# 202011AWSNP02.net
KiCad netlist of a schematic drawn in Altium Designer
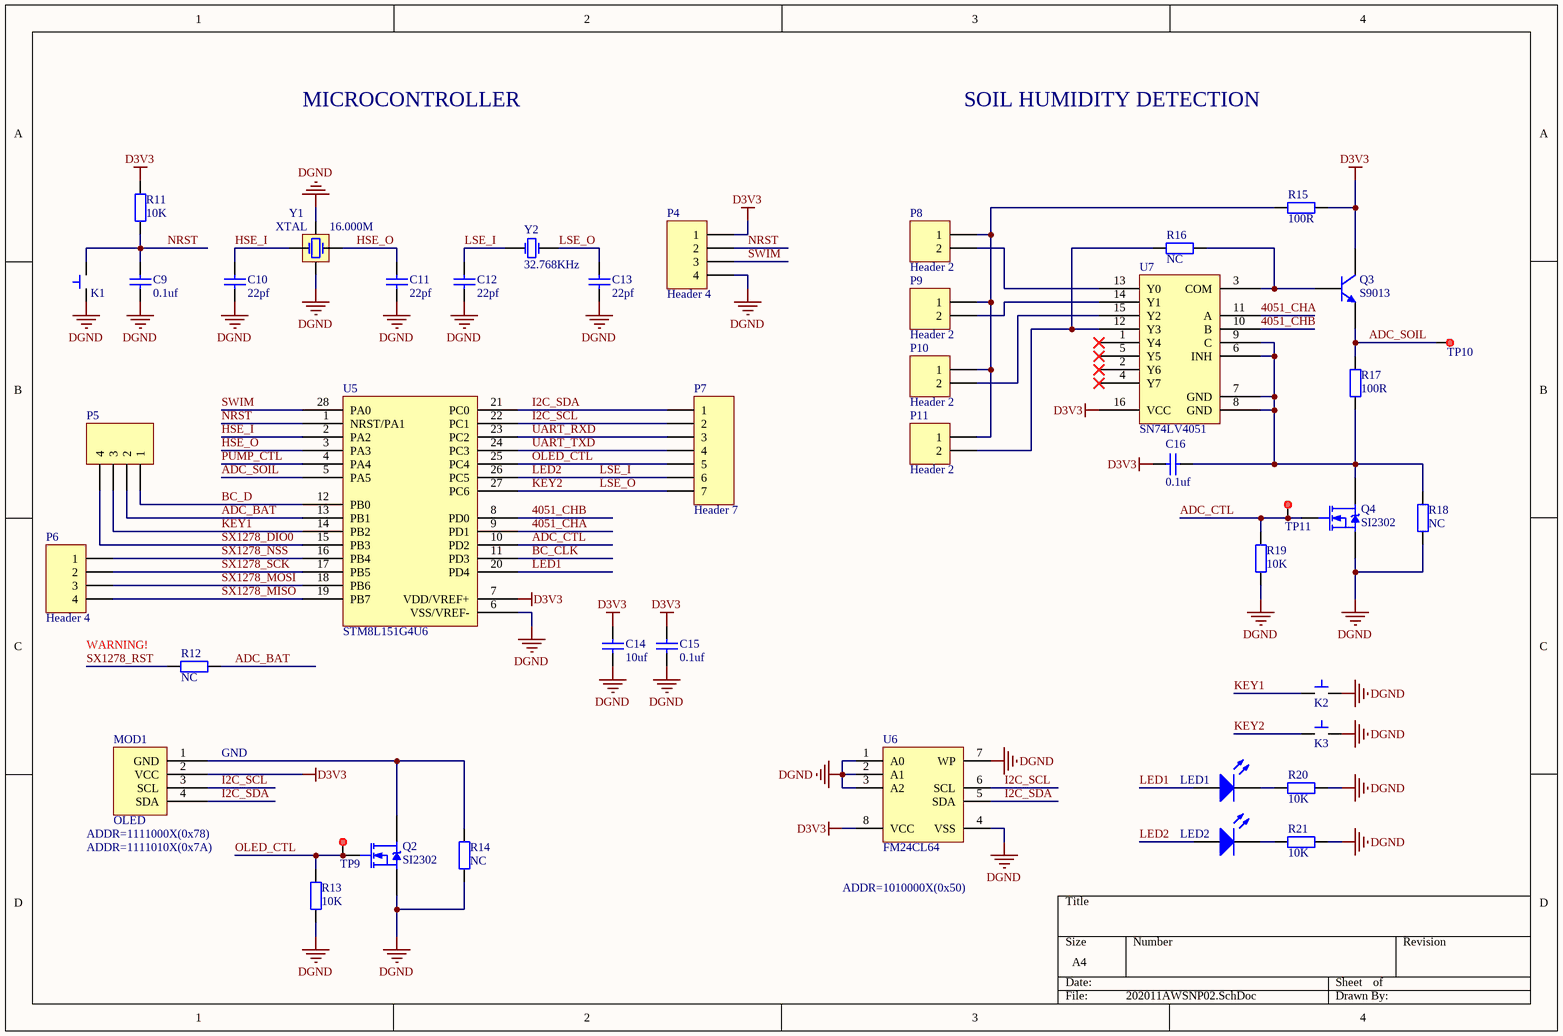
[diagram p0: 202011AWSNP02.SchDoc]

(export (version "E")
  (design (tool "Eeschema 10.0.6"))
  (components
    (comp (ref "C9")
      (value "0.1uf")
      (footprint "C0805")
      (fields (field (name "Comment") "Cap"))
      (libsource (lib "carrot_lib") (part "Cap"))
    )
    (comp (ref "C10")
      (value "22pf")
      (footprint "C0805")
      (fields (field (name "Comment") "Cap"))
      (libsource (lib "carrot_lib") (part "Cap"))
    )
    (comp (ref "C11")
      (value "22pf")
      (footprint "C0805")
      (fields (field (name "Comment") "Cap"))
      (libsource (lib "carrot_lib") (part "Cap"))
    )
    (comp (ref "C12")
      (value "22pf")
      (footprint "C0805")
      (fields (field (name "Comment") "Cap"))
      (libsource (lib "carrot_lib") (part "Cap"))
    )
    (comp (ref "C13")
      (value "22pf")
      (footprint "C0805")
      (fields (field (name "Comment") "Cap"))
      (libsource (lib "carrot_lib") (part "Cap"))
    )
    (comp (ref "C14")
      (value "10uf")
      (footprint "C0805")
      (fields (field (name "Comment") "Cap"))
      (libsource (lib "carrot_lib") (part "Cap"))
    )
    (comp (ref "C15")
      (value "0.1uf")
      (footprint "C0805")
      (fields (field (name "Comment") "Cap"))
      (libsource (lib "carrot_lib") (part "Cap"))
    )
    (comp (ref "C16")
      (value "0.1uf")
      (footprint "C0805")
      (fields (field (name "Comment") "Cap"))
      (libsource (lib "carrot_lib") (part "Cap"))
    )
    (comp (ref "K1")
      (value "Button")
      (footprint "Button-SMT-Small")
      (description "轻触开关")
      (libsource (lib "carrot_lib") (part "Button"))
    )
    (comp (ref "K2")
      (value "Button")
      (footprint "Button-SMT-Small")
      (description "轻触开关")
      (libsource (lib "carrot_lib") (part "Button"))
    )
    (comp (ref "K3")
      (value "Button")
      (footprint "Button-SMT-Small")
      (description "轻触开关")
      (libsource (lib "carrot_lib") (part "Button"))
    )
    (comp (ref "LED1") (value "LED") (footprint "LED1206") (libsource (lib "carrot_lib") (part "LED")))
    (comp (ref "LED2") (value "LED") (footprint "LED1206") (libsource (lib "carrot_lib") (part "LED")))
    (comp (ref "MOD1")
      (value "OLED")
      (footprint "MODULE OLED-4P-0.96")
      (description "OLED显示模块")
      (libsource (lib "carrot_lib") (part "Module OLED"))
    )
    (comp (ref "P4")
      (value "Header 4")
      (footprint "HDR1X4")
      (description "Header, 4-Pin")
      (fields (field (name "PUBLISHER") "Altium Limited"))
      (libsource (lib "Miscellaneous Connectors") (part "Header 4"))
    )
    (comp (ref "P5")
      (value "Header 4")
      (footprint "HDR1X4")
      (description "Header, 4-Pin")
      (fields (field (name "PUBLISHER") "Altium Limited"))
      (libsource (lib "") (part "Header 4_1"))
    )
    (comp (ref "P6")
      (value "Header 4")
      (footprint "HDR1X4")
      (description "Header, 4-Pin")
      (fields (field (name "PUBLISHER") "Altium Limited"))
      (libsource (lib "Miscellaneous Connectors") (part "Header 4"))
    )
    (comp (ref "P7")
      (value "Header 7")
      (footprint "HDR1X7")
      (description "Header, 7-Pin")
      (fields (field (name "PUBLISHER") "Altium Limited"))
      (libsource (lib "Miscellaneous Connectors") (part "Header 7"))
    )
    (comp (ref "P8")
      (value "Header 2")
      (footprint "HDR1X2")
      (description "Header, 2-Pin")
      (fields (field (name "PUBLISHER") "Altium Limited"))
      (libsource (lib "Miscellaneous Connectors") (part "Header 2"))
    )
    (comp (ref "P9")
      (value "Header 2")
      (footprint "HDR1X2")
      (description "Header, 2-Pin")
      (fields (field (name "PUBLISHER") "Altium Limited"))
      (libsource (lib "Miscellaneous Connectors") (part "Header 2"))
    )
    (comp (ref "P10")
      (value "Header 2")
      (footprint "HDR1X2")
      (description "Header, 2-Pin")
      (fields (field (name "PUBLISHER") "Altium Limited"))
      (libsource (lib "Miscellaneous Connectors") (part "Header 2"))
    )
    (comp (ref "P11")
      (value "Header 2")
      (footprint "HDR1X2")
      (description "Header, 2-Pin")
      (fields (field (name "PUBLISHER") "Altium Limited"))
      (libsource (lib "Miscellaneous Connectors") (part "Header 2"))
    )
    (comp (ref "Q2")
      (value "SI2302")
      (footprint "SI2302-SOT23")
      (description "N-Channel 20 V (D-S) MOSFET")
      (libsource (lib "carrot_lib") (part "SI2302"))
    )
    (comp (ref "Q3")
      (value "S9013")
      (footprint "SOT-23")
      (description "NPN General Purpose Amplifier")
      (libsource (lib "carrot_lib") (part "NPN"))
    )
    (comp (ref "Q4")
      (value "SI2302")
      (footprint "SI2302-SOT23")
      (description "N-Channel 20 V (D-S) MOSFET")
      (libsource (lib "carrot_lib") (part "SI2302"))
    )
    (comp (ref "R11")
      (value "10K")
      (footprint "R0805")
      (description "电阻")
      (fields (field (name "Comment") "Res"))
      (libsource (lib "carrot_lib") (part "Res"))
    )
    (comp (ref "R12")
      (value "NC")
      (footprint "R0805")
      (description "电阻")
      (fields (field (name "Comment") "Res"))
      (libsource (lib "carrot_lib") (part "Res"))
    )
    (comp (ref "R13")
      (value "10K")
      (footprint "R0805")
      (description "电阻")
      (fields (field (name "Comment") "Res"))
      (libsource (lib "") (part "Res_1"))
    )
    (comp (ref "R14")
      (value "NC")
      (footprint "R0805")
      (description "电阻")
      (fields (field (name "Comment") "Res"))
      (libsource (lib "") (part "Res_1"))
    )
    (comp (ref "R15")
      (value "100R")
      (footprint "R0805")
      (description "电阻")
      (fields (field (name "Comment") "Res"))
      (libsource (lib "") (part "Res_2"))
    )
    (comp (ref "R16")
      (value "NC")
      (footprint "R0805")
      (description "电阻")
      (fields (field (name "Comment") "Res"))
      (libsource (lib "") (part "Res_2"))
    )
    (comp (ref "R17")
      (value "100R")
      (footprint "R0805")
      (description "电阻")
      (fields (field (name "Comment") "Res"))
      (libsource (lib "") (part "Res_1"))
    )
    (comp (ref "R18")
      (value "NC")
      (footprint "R0805")
      (description "电阻")
      (fields (field (name "Comment") "Res"))
      (libsource (lib "") (part "Res_1"))
    )
    (comp (ref "R19")
      (value "10K")
      (footprint "R0805")
      (description "电阻")
      (fields (field (name "Comment") "Res"))
      (libsource (lib "") (part "Res_1"))
    )
    (comp (ref "R20")
      (value "10K")
      (footprint "R0805")
      (description "电阻")
      (fields (field (name "Comment") "Res"))
      (libsource (lib "") (part "Res_3"))
    )
    (comp (ref "R21")
      (value "10K")
      (footprint "R0805")
      (description "电阻")
      (fields (field (name "Comment") "Res"))
      (libsource (lib "") (part "Res_3"))
    )
    (comp (ref "TP9")
      (value "TestPoint")
      (footprint "TestPoint-R30")
      (description "测试点")
      (libsource (lib "carrot_lib") (part "TestPoint"))
    )
    (comp (ref "TP10")
      (value "TestPoint")
      (footprint "TestPoint-R30")
      (description "测试点")
      (libsource (lib "carrot_lib") (part "TestPoint"))
    )
    (comp (ref "TP11")
      (value "TestPoint")
      (footprint "TestPoint-R30")
      (description "测试点")
      (libsource (lib "carrot_lib") (part "TestPoint"))
    )
    (comp (ref "U5")
      (value "STM8L151G4U6")
      (footprint "STM8L151G4U6-UFQFN28")
      (libsource (lib "carrot_lib") (part "STM8L151G4U6"))
    )
    (comp (ref "U6")
      (value "FM24CL64")
      (footprint "FM24CL64-SOIC8")
      (description "64Kb Serial 3V FRAM Memory")
      (libsource (lib "carrot_lib") (part "FM24CL64"))
    )
    (comp (ref "U7")
      (value "SN74LV4051")
      (footprint "SN74LV4051-TSSOP16")
      (description "SN74LV4051A 8-Channel Analog Multiplexers and Demultiplexers")
      (libsource (lib "carrot_lib") (part "SN74LV4051"))
    )
    (comp (ref "Y1")
      (value "XTAL")
      (footprint "XTAL-3225")
      (description "无源晶振")
      (fields (field (name "ALTIUM_VALUE") "16.000M"))
      (libsource (lib "carrot_lib") (part "XTAL3"))
    )
    (comp (ref "Y2")
      (value "32.768KHz")
      (footprint "XTAL-3215")
      (description "Crystal Oscillator")
      (fields (field (name "Comment") "XTAL"))
      (libsource (lib "carrot_lib") (part "XTAL"))
    )
  )
  (nets
    (net (code "1") (name "/4051_CHA") (class "Default")
      (node (ref "U5") (pin "9") (pinfunction "PD1_9") (pintype "passive"))
      (node (ref "U7") (pin "11") (pinfunction "A_11") (pintype "passive"))
    )
    (net (code "2") (name "/4051_CHB") (class "Default")
      (node (ref "U5") (pin "8") (pinfunction "PD0_8") (pintype "passive"))
      (node (ref "U7") (pin "10") (pinfunction "B_10") (pintype "passive"))
    )
    (net (code "3") (name "/ADC_BAT") (class "Default")
      (node (ref "P5") (pin "2") (pinfunction "2_2") (pintype "passive"))
      (node (ref "R12") (pin "1") (pinfunction "1_1") (pintype "passive"))
      (node (ref "U5") (pin "13") (pinfunction "PB1_13") (pintype "passive"))
    )
    (net (code "4") (name "/ADC_CTL") (class "Default")
      (node (ref "Q4") (pin "1") (pinfunction "G_1") (pintype "passive"))
      (node (ref "R19") (pin "2") (pinfunction "2_2") (pintype "passive"))
      (node (ref "TP11") (pin "1") (pinfunction "1_1") (pintype "passive"))
      (node (ref "U5") (pin "10") (pinfunction "PD2_10") (pintype "passive"))
    )
    (net (code "5") (name "/ADC_SOIL") (class "Default")
      (node (ref "Q3") (pin "E") (pinfunction "E_E") (pintype "passive"))
      (node (ref "R17") (pin "2") (pinfunction "2_2") (pintype "passive"))
      (node (ref "TP10") (pin "1") (pinfunction "1_1") (pintype "passive"))
      (node (ref "U5") (pin "5") (pinfunction "PA5_5") (pintype "passive"))
    )
    (net (code "6") (name "/BC_CLK") (class "Default")
      (node (ref "U5") (pin "11") (pinfunction "PD3_11") (pintype "passive"))
    )
    (net (code "7") (name "/BC_D") (class "Default")
      (node (ref "P5") (pin "1") (pinfunction "1_1") (pintype "passive"))
      (node (ref "U5") (pin "12") (pinfunction "PB0_12") (pintype "passive"))
    )
    (net (code "8") (name "/HSE_I") (class "Default")
      (node (ref "C10") (pin "2") (pinfunction "2_2") (pintype "passive"))
      (node (ref "U5") (pin "2") (pinfunction "PA2_2") (pintype "passive"))
      (node (ref "Y1") (pin "1") (pinfunction "OSC1_1") (pintype "passive"))
    )
    (net (code "9") (name "/HSE_O") (class "Default")
      (node (ref "C11") (pin "2") (pinfunction "2_2") (pintype "passive"))
      (node (ref "U5") (pin "3") (pinfunction "PA3_3") (pintype "passive"))
      (node (ref "Y1") (pin "3") (pinfunction "OSC2_3") (pintype "passive"))
    )
    (net (code "10") (name "/I2C_SCL") (class "Default")
      (node (ref "MOD1") (pin "3") (pinfunction "SCL_3") (pintype "passive"))
      (node (ref "P7") (pin "2") (pinfunction "2_2") (pintype "passive"))
      (node (ref "U5") (pin "22") (pinfunction "PC1_22") (pintype "passive"))
      (node (ref "U6") (pin "6") (pinfunction "SCL_6") (pintype "passive"))
    )
    (net (code "11") (name "/I2C_SDA") (class "Default")
      (node (ref "MOD1") (pin "4") (pinfunction "SDA_4") (pintype "passive"))
      (node (ref "P7") (pin "1") (pinfunction "1_1") (pintype "passive"))
      (node (ref "U5") (pin "21") (pinfunction "PC0_21") (pintype "passive"))
      (node (ref "U6") (pin "5") (pinfunction "SDA_5") (pintype "passive"))
    )
    (net (code "12") (name "/KEY1") (class "Default")
      (node (ref "K2") (pin "1") (pinfunction "IN_1") (pintype "passive"))
      (node (ref "P5") (pin "3") (pinfunction "3_3") (pintype "passive"))
      (node (ref "U5") (pin "14") (pinfunction "PB2_14") (pintype "passive"))
    )
    (net (code "13") (name "/KEY2") (class "Default")
      (node (ref "C13") (pin "2") (pinfunction "2_2") (pintype "passive"))
      (node (ref "K3") (pin "1") (pinfunction "IN_1") (pintype "passive"))
      (node (ref "P7") (pin "7") (pinfunction "7_7") (pintype "passive"))
      (node (ref "U5") (pin "27") (pinfunction "PC6_27") (pintype "passive"))
      (node (ref "Y2") (pin "2") (pinfunction "OSC2_2") (pintype "passive"))
    )
    (net (code "14") (name "/LED1") (class "Default")
      (node (ref "LED1") (pin "1") (pinfunction "A_1") (pintype "passive"))
      (node (ref "U5") (pin "20") (pinfunction "PD4_20") (pintype "passive"))
    )
    (net (code "15") (name "/LED2") (class "Default")
      (node (ref "C12") (pin "2") (pinfunction "2_2") (pintype "passive"))
      (node (ref "LED2") (pin "1") (pinfunction "A_1") (pintype "passive"))
      (node (ref "P7") (pin "6") (pinfunction "6_6") (pintype "passive"))
      (node (ref "U5") (pin "26") (pinfunction "PC5_26") (pintype "passive"))
      (node (ref "Y2") (pin "1") (pinfunction "OSC1_1") (pintype "passive"))
    )
    (net (code "16") (name "/NRST") (class "Default")
      (node (ref "C9") (pin "2") (pinfunction "2_2") (pintype "passive"))
      (node (ref "K1") (pin "1") (pinfunction "IN_1") (pintype "passive"))
      (node (ref "P4") (pin "2") (pinfunction "2_2") (pintype "passive"))
      (node (ref "R11") (pin "2") (pinfunction "2_2") (pintype "passive"))
      (node (ref "U5") (pin "1") (pinfunction "NRST/PA1_1") (pintype "passive"))
    )
    (net (code "17") (name "/OLED_CTL") (class "Default")
      (node (ref "P7") (pin "5") (pinfunction "5_5") (pintype "passive"))
      (node (ref "Q2") (pin "1") (pinfunction "G_1") (pintype "passive"))
      (node (ref "R13") (pin "2") (pinfunction "2_2") (pintype "passive"))
      (node (ref "TP9") (pin "1") (pinfunction "1_1") (pintype "passive"))
      (node (ref "U5") (pin "25") (pinfunction "PC4_25") (pintype "passive"))
    )
    (net (code "18") (name "/PUMP_CTL") (class "Default")
      (node (ref "U5") (pin "4") (pinfunction "PA4_4") (pintype "passive"))
    )
    (net (code "19") (name "/SWIM") (class "Default")
      (node (ref "P4") (pin "3") (pinfunction "3_3") (pintype "passive"))
      (node (ref "U5") (pin "28") (pinfunction "PA0_28") (pintype "passive"))
    )
    (net (code "20") (name "/SX1278_DIO0") (class "Default")
      (node (ref "P5") (pin "4") (pinfunction "4_4") (pintype "passive"))
      (node (ref "U5") (pin "15") (pinfunction "PB3_15") (pintype "passive"))
    )
    (net (code "21") (name "/SX1278_MISO") (class "Default")
      (node (ref "P6") (pin "4") (pinfunction "4_4") (pintype "passive"))
      (node (ref "U5") (pin "19") (pinfunction "PB7_19") (pintype "passive"))
    )
    (net (code "22") (name "/SX1278_MOSI") (class "Default")
      (node (ref "P6") (pin "3") (pinfunction "3_3") (pintype "passive"))
      (node (ref "U5") (pin "18") (pinfunction "PB6_18") (pintype "passive"))
    )
    (net (code "23") (name "/SX1278_NSS") (class "Default")
      (node (ref "P6") (pin "1") (pinfunction "1_1") (pintype "passive"))
      (node (ref "U5") (pin "16") (pinfunction "PB4_16") (pintype "passive"))
    )
    (net (code "24") (name "/SX1278_RST") (class "Default")
      (node (ref "R12") (pin "2") (pinfunction "2_2") (pintype "passive"))
    )
    (net (code "25") (name "/SX1278_SCK") (class "Default")
      (node (ref "P6") (pin "2") (pinfunction "2_2") (pintype "passive"))
      (node (ref "U5") (pin "17") (pinfunction "PB5_17") (pintype "passive"))
    )
    (net (code "26") (name "/UART_RXD") (class "Default")
      (node (ref "P7") (pin "3") (pinfunction "3_3") (pintype "passive"))
      (node (ref "U5") (pin "23") (pinfunction "PC2_23") (pintype "passive"))
    )
    (net (code "27") (name "/UART_TXD") (class "Default")
      (node (ref "P7") (pin "4") (pinfunction "4_4") (pintype "passive"))
      (node (ref "U5") (pin "24") (pinfunction "PC3_24") (pintype "passive"))
    )
    (net (code "28") (name "D3V3") (class "Default")
      (node (ref "C14") (pin "2") (pinfunction "2_2") (pintype "passive"))
      (node (ref "C15") (pin "2") (pinfunction "2_2") (pintype "passive"))
      (node (ref "C16") (pin "2") (pinfunction "2_2") (pintype "passive"))
      (node (ref "MOD1") (pin "2") (pinfunction "VCC_2") (pintype "passive"))
      (node (ref "P4") (pin "1") (pinfunction "1_1") (pintype "passive"))
      (node (ref "Q3") (pin "C") (pinfunction "C_C") (pintype "passive"))
      (node (ref "R11") (pin "1") (pinfunction "1_1") (pintype "passive"))
      (node (ref "R15") (pin "2") (pinfunction "2_2") (pintype "passive"))
      (node (ref "U5") (pin "7") (pinfunction "VDD/VREF+_7") (pintype "passive"))
      (node (ref "U6") (pin "8") (pinfunction "VCC_8") (pintype "passive"))
      (node (ref "U7") (pin "16") (pinfunction "VCC_16") (pintype "passive"))
    )
    (net (code "29") (name "DGND") (class "Default")
      (node (ref "C10") (pin "1") (pinfunction "1_1") (pintype "passive"))
      (node (ref "C11") (pin "1") (pinfunction "1_1") (pintype "passive"))
      (node (ref "C12") (pin "1") (pinfunction "1_1") (pintype "passive"))
      (node (ref "C13") (pin "1") (pinfunction "1_1") (pintype "passive"))
      (node (ref "C14") (pin "1") (pinfunction "1_1") (pintype "passive"))
      (node (ref "C15") (pin "1") (pinfunction "1_1") (pintype "passive"))
      (node (ref "C9") (pin "1") (pinfunction "1_1") (pintype "passive"))
      (node (ref "K1") (pin "2") (pinfunction "OUT_2") (pintype "passive"))
      (node (ref "K2") (pin "2") (pinfunction "OUT_2") (pintype "passive"))
      (node (ref "K3") (pin "2") (pinfunction "OUT_2") (pintype "passive"))
      (node (ref "P4") (pin "4") (pinfunction "4_4") (pintype "passive"))
      (node (ref "Q2") (pin "2") (pinfunction "S_2") (pintype "passive"))
      (node (ref "Q4") (pin "2") (pinfunction "S_2") (pintype "passive"))
      (node (ref "R13") (pin "1") (pinfunction "1_1") (pintype "passive"))
      (node (ref "R14") (pin "1") (pinfunction "1_1") (pintype "passive"))
      (node (ref "R18") (pin "1") (pinfunction "1_1") (pintype "passive"))
      (node (ref "R19") (pin "1") (pinfunction "1_1") (pintype "passive"))
      (node (ref "R20") (pin "1") (pinfunction "1_1") (pintype "passive"))
      (node (ref "R21") (pin "1") (pinfunction "1_1") (pintype "passive"))
      (node (ref "U5") (pin "6") (pinfunction "VSS/VREF-_6") (pintype "passive"))
      (node (ref "U6") (pin "1") (pinfunction "A0_1") (pintype "passive"))
      (node (ref "U6") (pin "2") (pinfunction "A1_2") (pintype "passive"))
      (node (ref "U6") (pin "3") (pinfunction "A2_3") (pintype "passive"))
      (node (ref "U6") (pin "4") (pinfunction "VSS_4") (pintype "passive"))
      (node (ref "U6") (pin "7") (pinfunction "WP_7") (pintype "passive"))
      (node (ref "Y1") (pin "2") (pinfunction "GND_2") (pintype "passive"))
      (node (ref "Y1") (pin "4") (pinfunction "GND_4") (pintype "passive"))
    )
    (net (code "30") (name "Net-(LED1-K)") (class "Default")
      (node (ref "LED1") (pin "2") (pinfunction "K_2") (pintype "passive"))
      (node (ref "R20") (pin "2") (pinfunction "2_2") (pintype "passive"))
    )
    (net (code "31") (name "Net-(LED2-K)") (class "Default")
      (node (ref "LED2") (pin "2") (pinfunction "K_2") (pintype "passive"))
      (node (ref "R21") (pin "2") (pinfunction "2_2") (pintype "passive"))
    )
    (net (code "32") (name "Net-(MOD1-GND)") (class "Default")
      (node (ref "MOD1") (pin "1") (pinfunction "GND_1") (pintype "passive"))
      (node (ref "Q2") (pin "3") (pinfunction "D_3") (pintype "passive"))
      (node (ref "R14") (pin "2") (pinfunction "2_2") (pintype "passive"))
    )
    (net (code "33") (name "Net-(P10-Pad1)") (class "Default")
      (node (ref "P10") (pin "1") (pinfunction "1_1") (pintype "passive"))
      (node (ref "P11") (pin "1") (pinfunction "1_1") (pintype "passive"))
      (node (ref "P8") (pin "1") (pinfunction "1_1") (pintype "passive"))
      (node (ref "P9") (pin "1") (pinfunction "1_1") (pintype "passive"))
      (node (ref "R15") (pin "1") (pinfunction "1_1") (pintype "passive"))
    )
    (net (code "34") (name "Net-(Q4-D)") (class "Default")
      (node (ref "C16") (pin "1") (pinfunction "1_1") (pintype "passive"))
      (node (ref "Q4") (pin "3") (pinfunction "D_3") (pintype "passive"))
      (node (ref "R17") (pin "1") (pinfunction "1_1") (pintype "passive"))
      (node (ref "R18") (pin "2") (pinfunction "2_2") (pintype "passive"))
      (node (ref "U7") (pin "6") (pinfunction "INH_6") (pintype "passive"))
      (node (ref "U7") (pin "7") (pinfunction "GND_7") (pintype "passive"))
      (node (ref "U7") (pin "8") (pinfunction "GND_8") (pintype "passive"))
      (node (ref "U7") (pin "9") (pinfunction "C_9") (pintype "passive"))
    )
    (net (code "35") (name "Net-(U7-COM)") (class "Default")
      (node (ref "Q3") (pin "B") (pinfunction "B_B") (pintype "passive"))
      (node (ref "R16") (pin "2") (pinfunction "2_2") (pintype "passive"))
      (node (ref "U7") (pin "3") (pinfunction "COM_3") (pintype "passive"))
    )
    (net (code "36") (name "Net-(U7-Y0)") (class "Default")
      (node (ref "P8") (pin "2") (pinfunction "2_2") (pintype "passive"))
      (node (ref "U7") (pin "13") (pinfunction "Y0_13") (pintype "passive"))
    )
    (net (code "37") (name "Net-(U7-Y1)") (class "Default")
      (node (ref "P9") (pin "2") (pinfunction "2_2") (pintype "passive"))
      (node (ref "U7") (pin "14") (pinfunction "Y1_14") (pintype "passive"))
    )
    (net (code "38") (name "Net-(U7-Y2)") (class "Default")
      (node (ref "P10") (pin "2") (pinfunction "2_2") (pintype "passive"))
      (node (ref "U7") (pin "15") (pinfunction "Y2_15") (pintype "passive"))
    )
    (net (code "39") (name "Net-(U7-Y3)") (class "Default")
      (node (ref "P11") (pin "2") (pinfunction "2_2") (pintype "passive"))
      (node (ref "R16") (pin "1") (pinfunction "1_1") (pintype "passive"))
      (node (ref "U7") (pin "12") (pinfunction "Y3_12") (pintype "passive"))
    )
    (net (code "40") (name "unconnected-(U7-Y4-Pad1)") (class "Default")
      (node (ref "U7") (pin "1") (pinfunction "Y4_1") (pintype "passive+no_connect"))
    )
    (net (code "41") (name "unconnected-(U7-Y5-Pad5)") (class "Default")
      (node (ref "U7") (pin "5") (pinfunction "Y5_5") (pintype "passive+no_connect"))
    )
    (net (code "42") (name "unconnected-(U7-Y6-Pad2)") (class "Default")
      (node (ref "U7") (pin "2") (pinfunction "Y6_2") (pintype "passive+no_connect"))
    )
    (net (code "43") (name "unconnected-(U7-Y7-Pad4)") (class "Default")
      (node (ref "U7") (pin "4") (pinfunction "Y7_4") (pintype "passive+no_connect"))
    )
  )
)
